# rv_pwr_es_sensor.net
KiCad netlist of a schematic drawn in Altium Designer
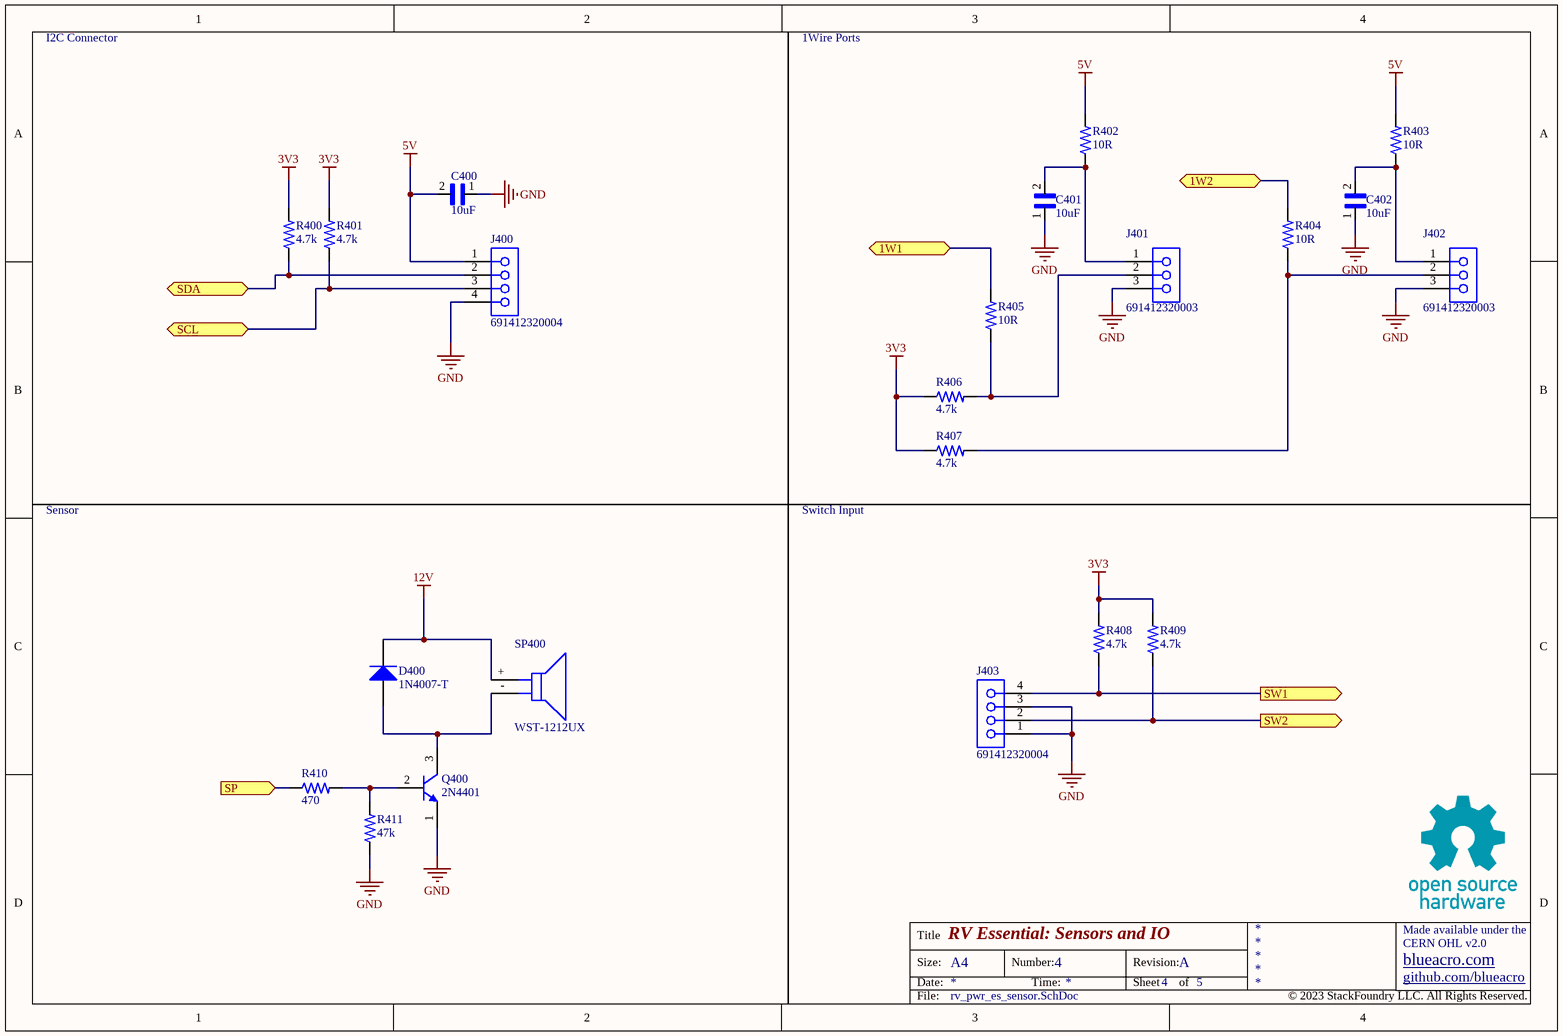
[diagram p0: rv_pwr_es_sensor.SchDoc]

(export (version "E")
  (design (tool "Eeschema 10.0.6"))
  (components
    (comp (ref "C400")
      (value "10uF")
      (footprint "CAPRB250W50L550T350H600")
      (description "FG Series 10 uF 25 V ±10% Tolerance X7R Radial Multilayer Ceramic Capacitor")
      (fields (field (name "MF") "TDK") (field (name "DIGI-KEY_PART_NUMBER") "445-173156-1-ND"))
      (libsource (lib "") (part "FG16X7R1E106KRT06_1"))
    )
    (comp (ref "C401")
      (value "10uF")
      (footprint "CAPRB250W50L550T350H600")
      (description "FG Series 10 uF 25 V ±10% Tolerance X7R Radial Multilayer Ceramic Capacitor")
      (fields (field (name "MF") "TDK") (field (name "DIGI-KEY_PART_NUMBER") "445-173156-1-ND"))
      (libsource (lib "StackFoundry LLC") (part "FG16X7R1E106KRT06"))
    )
    (comp (ref "C402")
      (value "10uF")
      (footprint "CAPRB250W50L550T350H600")
      (description "FG Series 10 uF 25 V ±10% Tolerance X7R Radial Multilayer Ceramic Capacitor")
      (fields (field (name "MF") "TDK") (field (name "DIGI-KEY_PART_NUMBER") "445-173156-1-ND"))
      (libsource (lib "StackFoundry LLC") (part "FG16X7R1E106KRT06"))
    )
    (comp (ref "D400")
      (value "1N4007-T")
      (footprint "DIOD-DO-41-P-2_V2")
      (description "VR=1000V IF=1A 8pF")
      (libsource (lib "StackFoundry LLC") (part "DIOD-D-A1K2-2"))
    )
    (comp (ref "J400")
      (value "691412320004")
      (footprint "691412320004")
      (description "Tb, Wire To Brd, 4Way, 16Awg Rohs Compliant: Yes")
      (libsource (lib "StackFoundry LLC") (part "TBL - 1R - 04P - Female"))
    )
    (comp (ref "J401")
      (value "691412320003")
      (footprint "691412320003")
      (description "Tb, Wire To Brd, 3Way, 16Awg Rohs Compliant: Yes")
      (libsource (lib "StackFoundry LLC") (part "TBL - 1R - 03P - Female"))
    )
    (comp (ref "J402")
      (value "691412320003")
      (footprint "691412320003")
      (description "Tb, Wire To Brd, 3Way, 16Awg Rohs Compliant: Yes")
      (libsource (lib "StackFoundry LLC") (part "TBL - 1R - 03P - Female"))
    )
    (comp (ref "J403")
      (value "691412320004")
      (footprint "691412320004")
      (description "Tb, Wire To Brd, 4Way, 16Awg Rohs Compliant: Yes")
      (libsource (lib "StackFoundry LLC") (part "TBL - 1R - 04P - Female"))
    )
    (comp (ref "Q400")
      (value "2N4401")
      (footprint "ONSC-TO-92-3-29-11")
      (description "Transistor NPN Silicon 40V IC=600ma TO-92 Case General Purpose Amplifier And Switch")
      (fields (field (name "MF") "Rectron"))
      (libsource (lib "StackFoundry LLC") (part "ONSC-NPN-E1B2C3-3"))
    )
    (comp (ref "R400")
      (value "4.7k")
      (footprint "0207/10 - Cloned")
      (description "Res Carbon Film 4.7K Ohm 5% 1/4W -500ppm/°C to 350ppm/°C Conformal AXL Thru-Hole Paper T/R")
      (fields (field (name "Comment") "4.7k TH 0207 5% 1/4W"))
      (libsource (lib "StackFoundry LLC") (part "R-US"))
    )
    (comp (ref "R401")
      (value "4.7k")
      (footprint "0207/10 - Cloned")
      (description "Res Carbon Film 4.7K Ohm 5% 1/4W -500ppm/°C to 350ppm/°C Conformal AXL Thru-Hole Paper T/R")
      (fields (field (name "Comment") "4.7k TH 0207 5% 1/4W"))
      (libsource (lib "StackFoundry LLC") (part "R-US"))
    )
    (comp (ref "R402")
      (value "10R")
      (footprint "0207/10")
      (description "Res Carbon Film 10 Ohm 5% 1/4W -500ppm/°C to 350ppm/°C Conformal AXL Thru-Hole Paper T/R")
      (fields (field (name "Comment") "10R TH 0207 5% 1/4W"))
      (libsource (lib "StackFoundry LLC") (part "R-US"))
    )
    (comp (ref "R403")
      (value "10R")
      (footprint "0207/10")
      (description "Res Carbon Film 10 Ohm 5% 1/4W -500ppm/°C to 350ppm/°C Conformal AXL Thru-Hole Paper T/R")
      (fields (field (name "Comment") "10R TH 0207 5% 1/4W"))
      (libsource (lib "StackFoundry LLC") (part "R-US"))
    )
    (comp (ref "R404")
      (value "10R")
      (footprint "0207/10")
      (description "Res Carbon Film 10 Ohm 5% 1/4W -500ppm/°C to 350ppm/°C Conformal AXL Thru-Hole Paper T/R")
      (fields (field (name "Comment") "10R TH 0207 5% 1/4W"))
      (libsource (lib "StackFoundry LLC") (part "R-US"))
    )
    (comp (ref "R405")
      (value "10R")
      (footprint "0207/10")
      (description "Res Carbon Film 10 Ohm 5% 1/4W -500ppm/°C to 350ppm/°C Conformal AXL Thru-Hole Paper T/R")
      (fields (field (name "Comment") "10R TH 0207 5% 1/4W"))
      (libsource (lib "StackFoundry LLC") (part "R-US"))
    )
    (comp (ref "R406")
      (value "4.7k")
      (footprint "0207/10 - Cloned")
      (description "Res Carbon Film 4.7K Ohm 5% 1/4W -500ppm/°C to 350ppm/°C Conformal AXL Thru-Hole Paper T/R")
      (fields (field (name "Comment") "4.7k TH 0207 5% 1/4W"))
      (libsource (lib "StackFoundry LLC") (part "R-US"))
    )
    (comp (ref "R407")
      (value "4.7k")
      (footprint "0207/10 - Cloned")
      (description "Res Carbon Film 4.7K Ohm 5% 1/4W -500ppm/°C to 350ppm/°C Conformal AXL Thru-Hole Paper T/R")
      (fields (field (name "Comment") "4.7k TH 0207 5% 1/4W"))
      (libsource (lib "StackFoundry LLC") (part "R-US"))
    )
    (comp (ref "R408")
      (value "4.7k")
      (footprint "0207/10 - Cloned")
      (description "Res Carbon Film 4.7K Ohm 5% 1/4W -500ppm/°C to 350ppm/°C Conformal AXL Thru-Hole Paper T/R")
      (fields (field (name "Comment") "4.7k TH 0207 5% 1/4W"))
      (libsource (lib "StackFoundry LLC") (part "R-US"))
    )
    (comp (ref "R409")
      (value "4.7k")
      (footprint "0207/10 - Cloned")
      (description "Res Carbon Film 4.7K Ohm 5% 1/4W -500ppm/°C to 350ppm/°C Conformal AXL Thru-Hole Paper T/R")
      (fields (field (name "Comment") "4.7k TH 0207 5% 1/4W"))
      (libsource (lib "StackFoundry LLC") (part "R-US"))
    )
    (comp (ref "R410")
      (value "470")
      (footprint "0207/10")
      (description "Res Carbon Film 470 Ohm 5% 1/4W -500ppm/°C to 350ppm/°C Conformal AXL Thru-Hole Paper T/R")
      (fields (field (name "Comment") "470 TH 0207 5% 0.25W"))
      (libsource (lib "StackFoundry LLC") (part "R-US"))
    )
    (comp (ref "R411")
      (value "47k")
      (footprint "0207/10 - Cloned")
      (description "Res Carbon Film 47K Ohm 5% 1/4W -500ppm/°C to 350ppm/°C Conformal AXL Thru-Hole Paper T/R")
      (fields (field (name "Comment") "47k TH 0207 5% 1/4W"))
      (libsource (lib "StackFoundry LLC") (part "R-US"))
    )
    (comp (ref "SP400")
      (value "WST-1212UX")
      (footprint "WST-1212UX-Footprint-1")
      (description "Audio Magnetic Xdcr 9-15V Th")
      (libsource (lib "StackFoundry LLC") (part "WST-1212UX-Symbol-1"))
    )
  )
  (nets
    (net (code "1") (name "/1W1") (class "Default")
      (node (ref "R405") (pin "2") (pinfunction "2_2") (pintype "passive"))
    )
    (net (code "2") (name "/1W2") (class "Default")
      (node (ref "R404") (pin "2") (pinfunction "2_2") (pintype "passive"))
    )
    (net (code "3") (name "/SCL") (class "Default")
      (node (ref "J400") (pin "3") (pinfunction "3_3") (pintype "passive"))
      (node (ref "R401") (pin "1") (pinfunction "1_1") (pintype "passive"))
    )
    (net (code "4") (name "/SDA") (class "Default")
      (node (ref "J400") (pin "2") (pinfunction "2_2") (pintype "passive"))
      (node (ref "R400") (pin "1") (pinfunction "1_1") (pintype "passive"))
    )
    (net (code "5") (name "/SP") (class "Default")
      (node (ref "R410") (pin "1") (pinfunction "1_1") (pintype "passive"))
    )
    (net (code "6") (name "/SW1") (class "Default")
      (node (ref "J403") (pin "4") (pinfunction "4_4") (pintype "passive"))
      (node (ref "R408") (pin "1") (pinfunction "1_1") (pintype "passive"))
    )
    (net (code "7") (name "/SW2") (class "Default")
      (node (ref "J403") (pin "2") (pinfunction "2_2") (pintype "passive"))
      (node (ref "R409") (pin "1") (pinfunction "1_1") (pintype "passive"))
    )
    (net (code "8") (name "3V3") (class "Default")
      (node (ref "R400") (pin "2") (pinfunction "2_2") (pintype "passive"))
      (node (ref "R401") (pin "2") (pinfunction "2_2") (pintype "passive"))
      (node (ref "R406") (pin "1") (pinfunction "1_1") (pintype "passive"))
      (node (ref "R407") (pin "1") (pinfunction "1_1") (pintype "passive"))
      (node (ref "R408") (pin "2") (pinfunction "2_2") (pintype "passive"))
      (node (ref "R409") (pin "2") (pinfunction "2_2") (pintype "passive"))
    )
    (net (code "9") (name "5V") (class "Default")
      (node (ref "C400") (pin "2") (pinfunction "2_2") (pintype "passive"))
      (node (ref "J400") (pin "1") (pinfunction "1_1") (pintype "passive"))
      (node (ref "R402") (pin "2") (pinfunction "2_2") (pintype "passive"))
      (node (ref "R403") (pin "2") (pinfunction "2_2") (pintype "passive"))
    )
    (net (code "10") (name "12V") (class "Default")
      (node (ref "D400") (pin "2") (pinfunction "K_2") (pintype "passive"))
      (node (ref "SP400") (pin "+") (pinfunction "+_+") (pintype "passive"))
    )
    (net (code "11") (name "GND") (class "Default")
      (node (ref "C400") (pin "1") (pinfunction "1_1") (pintype "passive"))
      (node (ref "C401") (pin "1") (pinfunction "1_1") (pintype "passive"))
      (node (ref "C402") (pin "1") (pinfunction "1_1") (pintype "passive"))
      (node (ref "J400") (pin "4") (pinfunction "4_4") (pintype "passive"))
      (node (ref "J401") (pin "3") (pinfunction "3_3") (pintype "passive"))
      (node (ref "J402") (pin "3") (pinfunction "3_3") (pintype "passive"))
      (node (ref "J403") (pin "1") (pinfunction "1_1") (pintype "passive"))
      (node (ref "J403") (pin "3") (pinfunction "3_3") (pintype "passive"))
      (node (ref "Q400") (pin "1") (pinfunction "E_1") (pintype "passive"))
      (node (ref "R411") (pin "1") (pinfunction "1_1") (pintype "passive"))
    )
    (net (code "12") (name "Net-(C401-Pad2)") (class "Default")
      (node (ref "C401") (pin "2") (pinfunction "2_2") (pintype "passive"))
      (node (ref "J401") (pin "1") (pinfunction "1_1") (pintype "passive"))
      (node (ref "R402") (pin "1") (pinfunction "1_1") (pintype "passive"))
    )
    (net (code "13") (name "Net-(C402-Pad2)") (class "Default")
      (node (ref "C402") (pin "2") (pinfunction "2_2") (pintype "passive"))
      (node (ref "J402") (pin "1") (pinfunction "1_1") (pintype "passive"))
      (node (ref "R403") (pin "1") (pinfunction "1_1") (pintype "passive"))
    )
    (net (code "14") (name "Net-(D400-A)") (class "Default")
      (node (ref "D400") (pin "1") (pinfunction "A_1") (pintype "passive"))
      (node (ref "Q400") (pin "3") (pinfunction "C_3") (pintype "passive"))
      (node (ref "SP400") (pin "-") (pinfunction "-_-") (pintype "passive"))
    )
    (net (code "15") (name "Net-(J401-Pad2)") (class "Default")
      (node (ref "J401") (pin "2") (pinfunction "2_2") (pintype "passive"))
      (node (ref "R405") (pin "1") (pinfunction "1_1") (pintype "passive"))
      (node (ref "R406") (pin "2") (pinfunction "2_2") (pintype "passive"))
    )
    (net (code "16") (name "Net-(J402-Pad2)") (class "Default")
      (node (ref "J402") (pin "2") (pinfunction "2_2") (pintype "passive"))
      (node (ref "R404") (pin "1") (pinfunction "1_1") (pintype "passive"))
      (node (ref "R407") (pin "2") (pinfunction "2_2") (pintype "passive"))
    )
    (net (code "17") (name "Net-(Q400-B)") (class "Default")
      (node (ref "Q400") (pin "2") (pinfunction "B_2") (pintype "passive"))
      (node (ref "R410") (pin "2") (pinfunction "2_2") (pintype "passive"))
      (node (ref "R411") (pin "2") (pinfunction "2_2") (pintype "passive"))
    )
  )
)
